# Ethernet.net
KiCad netlist of a schematic drawn in Altium Designer
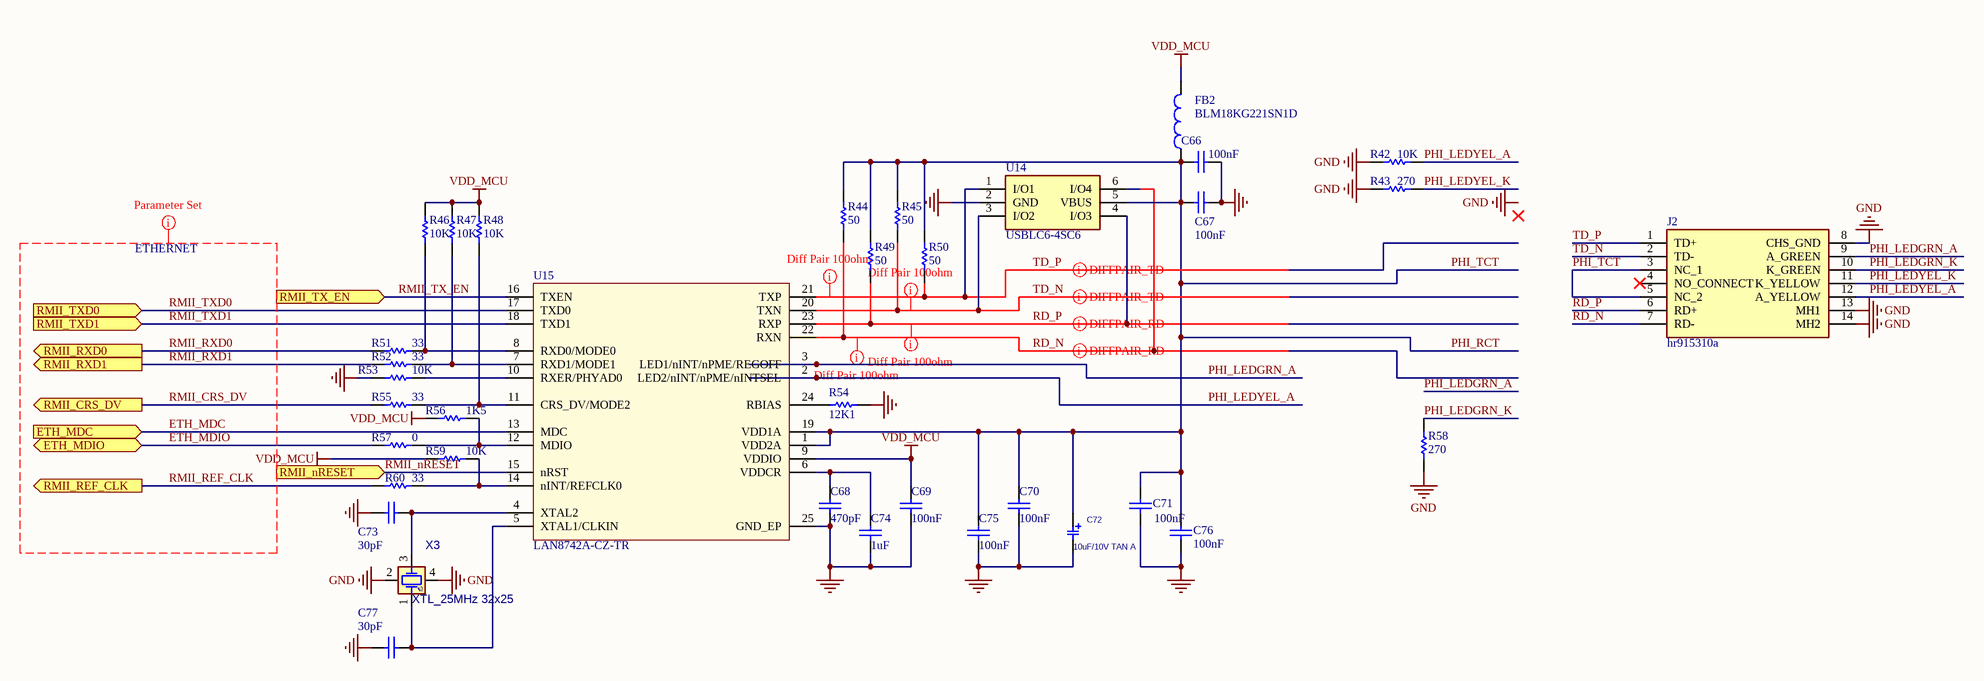
[diagram p0: Ethernet.SchDoc]

(export (version "E")
  (design (tool "Eeschema 10.0.6"))
  (components
    (comp (ref "C66") (value "100nF") (footprint "C0603") (libsource (lib "MCD_TOOLS") (part "Capacitor_ST")))
    (comp (ref "C67") (value "100nF") (footprint "C0603") (libsource (lib "MCD_TOOLS") (part "Capacitor_ST")))
    (comp (ref "C68") (value "470pF") (footprint "C0603") (libsource (lib "MCD_TOOLS") (part "Capacitor_ST")))
    (comp (ref "C69") (value "100nF") (footprint "C0603") (libsource (lib "MCD_TOOLS") (part "Capacitor_ST")))
    (comp (ref "C70") (value "100nF") (footprint "C0603") (libsource (lib "MCD_TOOLS") (part "Capacitor_ST")))
    (comp (ref "C71") (value "100nF") (footprint "C0603") (libsource (lib "MCD_TOOLS") (part "Capacitor_ST")))
    (comp (ref "C72")
      (value "10uF/10V TAN A")
      (footprint "C_TN_3216")
      (description "CAP, SMD, TAN")
      (fields (field (name "MANF") "VISHAY") (field (name "MANF_P#") "T55A106M6R3C0300"))
      (libsource (lib "CapTantal_passive") (part "CAP_SMD_TAN_10uF_6.3V"))
    )
    (comp (ref "C73") (value "30pF") (footprint "C0603") (libsource (lib "MCD_TOOLS") (part "Capacitor_ST")))
    (comp (ref "C74")
      (value "1uF")
      (footprint "C0603")
      (description "0603  X5R 1µF")
      (fields (field (name "TOLERANCE") "10%"))
      (libsource (lib "MB963_1") (part "CAP SMD 0603  X5R 1µF 25V 10%"))
    )
    (comp (ref "C75") (value "100nF") (footprint "C0603") (libsource (lib "MCD_TOOLS") (part "Capacitor_ST")))
    (comp (ref "C76") (value "100nF") (footprint "C0603") (libsource (lib "MCD_TOOLS") (part "Capacitor_ST")))
    (comp (ref "C77") (value "30pF") (footprint "C0603") (libsource (lib "MCD_TOOLS") (part "Capacitor_ST")))
    (comp (ref "FB2")
      (value "BLM18KG221SN1D")
      (footprint "L0603E")
      (description "Ferrite Bead")
      (fields (field (name "PUBLISHER") "Altium Limited"))
      (libsource (lib "Miscellaneous Devices") (part "Inductor"))
    )
    (comp (ref "J2")
      (value "hr915310a")
      (footprint "SamacSys:hr915310a")
      (description "HR915310A")
      (libsource (lib "*") (part "hr915310a"))
    )
    (comp (ref "R42") (value "10K") (footprint "R0603") (libsource (lib "") (part "Res1_1")))
    (comp (ref "R43") (value "270") (footprint "R0603") (libsource (lib "") (part "Res1_1")))
    (comp (ref "R44") (value "50") (footprint "R0603") (libsource (lib "MB1137") (part "Res_50_1%_0603")))
    (comp (ref "R45") (value "50") (footprint "R0603") (libsource (lib "MB1137") (part "Res_50_1%_0603")))
    (comp (ref "R46") (value "10K") (footprint "R0603") (libsource (lib "") (part "Res1_1")))
    (comp (ref "R47") (value "10K") (footprint "R0603") (libsource (lib "") (part "Res1_1")))
    (comp (ref "R48") (value "10K") (footprint "R0603") (libsource (lib "") (part "Res1_1")))
    (comp (ref "R49") (value "50") (footprint "R0603") (libsource (lib "MB1137") (part "Res_50_1%_0603")))
    (comp (ref "R50") (value "50") (footprint "R0603") (libsource (lib "MB1137") (part "Res_50_1%_0603")))
    (comp (ref "R51") (value "33") (footprint "R0603") (libsource (lib "MCD_TOOLS") (part "Res_33_1%_0402")))
    (comp (ref "R52") (value "33") (footprint "R0603") (libsource (lib "MCD_TOOLS") (part "Res_33_1%_0402")))
    (comp (ref "R53") (value "10K") (footprint "R0603") (libsource (lib "") (part "Res1_1")))
    (comp (ref "R54")
      (value "12K1")
      (footprint "R0603")
      (libsource (lib "MCD_TOOLS") (part "Res_12K1_1%_0603"))
    )
    (comp (ref "R55") (value "33") (footprint "R0603") (libsource (lib "MCD_TOOLS") (part "Res_33_1%_0402")))
    (comp (ref "R56")
      (value "1K5")
      (footprint "R0603")
      (libsource (lib "MCD_TOOLS") (part "Res_1K5_1%_0402"))
    )
    (comp (ref "R57")
      (value "0")
      (footprint "R0603")
      (fields (field (name "PUBLISHER") "Altium Limited"))
      (libsource (lib "Miscellaneous Devices") (part "Res1"))
    )
    (comp (ref "R58") (value "270") (footprint "R0603") (libsource (lib "") (part "Res1_1")))
    (comp (ref "R59") (value "10K") (footprint "R0603") (libsource (lib "") (part "Res1_1")))
    (comp (ref "R60") (value "33") (footprint "R0603") (libsource (lib "MCD_TOOLS") (part "Res_33_1%_0402")))
    (comp (ref "U14")
      (value "USBLC6-4SC6")
      (footprint "SamacSys:SOT95P280X145-6N")
      (description "Integrated Circuit")
      (fields (field (name "MOUSER PART NUMBER") "511-USBLC6-4SC6"))
      (libsource (lib "*") (part "USBLC6-4SC6"))
    )
    (comp (ref "U15")
      (value "LAN8742A-CZ-TR")
      (footprint "QFN50P400X400X100-25N-D")
      (libsource (lib "MB1137") (part "LAN8742A-CZ-TR"))
    )
    (comp (ref "X3")
      (value "XTL_25MHz 32x25")
      (footprint "XTL_4_3225")
      (description "CRYSTAL 25.00 MHZ 18pF, 10PPM")
      (fields (field (name "MANF") "EPSON") (field (name "MANF_P#") "TSX-3225 25.0000MF10P-C3"))
      (libsource (lib "crystal_osc") (part "XTL_4_25MHz_3225"))
    )
  )
  (nets
    (net (code "1") (name "/ETH_MDC") (class "Default")
      (node (ref "U15") (pin "13") (pinfunction "MDC_13") (pintype "passive"))
    )
    (net (code "2") (name "/ETH_MDIO") (class "Default")
      (node (ref "R57") (pin "2") (pinfunction "2_2") (pintype "passive"))
    )
    (net (code "3") (name "/PHI_LEDGRN_A") (class "Default")
      (node (ref "J2") (pin "9") (pinfunction "A_GREEN_9") (pintype "passive"))
      (node (ref "U15") (pin "3") (pinfunction "LED1/nINT/nPME/REGOFF_3") (pintype "passive"))
    )
    (net (code "4") (name "/PHI_LEDGRN_K") (class "Default")
      (node (ref "J2") (pin "10") (pinfunction "K_GREEN_10") (pintype "passive"))
      (node (ref "R58") (pin "1") (pinfunction "1_1") (pintype "passive"))
    )
    (net (code "5") (name "/PHI_LEDYEL_A") (class "Default")
      (node (ref "J2") (pin "12") (pinfunction "A_YELLOW_12") (pintype "passive"))
      (node (ref "R42") (pin "2") (pinfunction "2_2") (pintype "passive"))
      (node (ref "U15") (pin "2") (pinfunction "LED2/nINT/nPME/nINTSEL_2") (pintype "passive"))
    )
    (net (code "6") (name "/PHI_LEDYEL_K") (class "Default")
      (node (ref "J2") (pin "11") (pinfunction "K_YELLOW_11") (pintype "passive"))
      (node (ref "R43") (pin "2") (pinfunction "2_2") (pintype "passive"))
    )
    (net (code "7") (name "/PHI_RCT") (class "Default")
      (node (ref "C66") (pin "2") (pinfunction "2_2") (pintype "passive"))
      (node (ref "C67") (pin "2") (pinfunction "2_2") (pintype "passive"))
      (node (ref "C70") (pin "2") (pinfunction "2_2") (pintype "passive"))
      (node (ref "C71") (pin "2") (pinfunction "2_2") (pintype "passive"))
      (node (ref "C72") (pin "1") (pinfunction "1_1") (pintype "passive"))
      (node (ref "C75") (pin "2") (pinfunction "2_2") (pintype "passive"))
      (node (ref "C76") (pin "2") (pinfunction "2_2") (pintype "passive"))
      (node (ref "FB2") (pin "1") (pinfunction "1_1") (pintype "passive"))
      (node (ref "J2") (pin "3") (pinfunction "NC_1_3") (pintype "passive"))
      (node (ref "J2") (pin "5") (pinfunction "NC_2_5") (pintype "passive"))
      (node (ref "R44") (pin "2") (pinfunction "2_2") (pintype "passive"))
      (node (ref "R45") (pin "2") (pinfunction "2_2") (pintype "passive"))
      (node (ref "R49") (pin "2") (pinfunction "2_2") (pintype "passive"))
      (node (ref "R50") (pin "2") (pinfunction "2_2") (pintype "passive"))
      (node (ref "U14") (pin "5") (pinfunction "VBUS_5") (pintype "passive"))
      (node (ref "U15") (pin "1") (pinfunction "VDD2A_1") (pintype "passive"))
      (node (ref "U15") (pin "19") (pinfunction "VDD1A_19") (pintype "passive"))
    )
    (net (code "8") (name "/RD_N") (class "Default")
      (node (ref "J2") (pin "7") (pinfunction "RD-_7") (pintype "passive"))
      (node (ref "R44") (pin "1") (pinfunction "1_1") (pintype "passive"))
      (node (ref "U14") (pin "6") (pinfunction "I/O4_6") (pintype "passive"))
      (node (ref "U15") (pin "22") (pinfunction "RXN_22") (pintype "passive"))
    )
    (net (code "9") (name "/RD_P") (class "Default")
      (node (ref "J2") (pin "6") (pinfunction "RD+_6") (pintype "passive"))
      (node (ref "R49") (pin "1") (pinfunction "1_1") (pintype "passive"))
      (node (ref "U14") (pin "4") (pinfunction "I/O3_4") (pintype "passive"))
      (node (ref "U15") (pin "23") (pinfunction "RXP_23") (pintype "passive"))
    )
    (net (code "10") (name "/RMII_CRS_DV") (class "Default")
      (node (ref "R55") (pin "2") (pinfunction "2_2") (pintype "passive"))
    )
    (net (code "11") (name "/RMII_REF_CLK") (class "Default")
      (node (ref "R60") (pin "2") (pinfunction "2_2") (pintype "passive"))
    )
    (net (code "12") (name "/RMII_RXD0") (class "Default")
      (node (ref "R51") (pin "2") (pinfunction "2_2") (pintype "passive"))
    )
    (net (code "13") (name "/RMII_RXD1") (class "Default")
      (node (ref "R52") (pin "2") (pinfunction "2_2") (pintype "passive"))
    )
    (net (code "14") (name "/RMII_TXD0") (class "Default")
      (node (ref "U15") (pin "17") (pinfunction "TXD0_17") (pintype "passive"))
    )
    (net (code "15") (name "/RMII_TXD1") (class "Default")
      (node (ref "U15") (pin "18") (pinfunction "TXD1_18") (pintype "passive"))
    )
    (net (code "16") (name "/RMII_TX_EN") (class "Default")
      (node (ref "U15") (pin "16") (pinfunction "TXEN_16") (pintype "passive"))
    )
    (net (code "17") (name "/RMII_nRESET") (class "Default")
      (node (ref "U15") (pin "15") (pinfunction "nRST_15") (pintype "passive"))
    )
    (net (code "18") (name "/TD_N") (class "Default")
      (node (ref "J2") (pin "2") (pinfunction "TD-_2") (pintype "passive"))
      (node (ref "R45") (pin "1") (pinfunction "1_1") (pintype "passive"))
      (node (ref "U14") (pin "3") (pinfunction "I/O2_3") (pintype "passive"))
      (node (ref "U15") (pin "20") (pinfunction "TXN_20") (pintype "passive"))
    )
    (net (code "19") (name "/TD_P") (class "Default")
      (node (ref "J2") (pin "1") (pinfunction "TD+_1") (pintype "passive"))
      (node (ref "R50") (pin "1") (pinfunction "1_1") (pintype "passive"))
      (node (ref "U14") (pin "1") (pinfunction "I/O1_1") (pintype "passive"))
      (node (ref "U15") (pin "21") (pinfunction "TXP_21") (pintype "passive"))
    )
    (net (code "20") (name "GND") (class "Default")
      (node (ref "C66") (pin "1") (pinfunction "1_1") (pintype "passive"))
      (node (ref "C67") (pin "1") (pinfunction "1_1") (pintype "passive"))
      (node (ref "C68") (pin "1") (pinfunction "1_1") (pintype "passive"))
      (node (ref "C69") (pin "1") (pinfunction "1_1") (pintype "passive"))
      (node (ref "C70") (pin "1") (pinfunction "1_1") (pintype "passive"))
      (node (ref "C71") (pin "1") (pinfunction "1_1") (pintype "passive"))
      (node (ref "C72") (pin "2") (pinfunction "2_2") (pintype "passive"))
      (node (ref "C73") (pin "2") (pinfunction "2_2") (pintype "passive"))
      (node (ref "C74") (pin "2") (pinfunction "2_2") (pintype "passive"))
      (node (ref "C75") (pin "1") (pinfunction "1_1") (pintype "passive"))
      (node (ref "C76") (pin "1") (pinfunction "1_1") (pintype "passive"))
      (node (ref "C77") (pin "2") (pinfunction "2_2") (pintype "passive"))
      (node (ref "J2") (pin "13") (pinfunction "MH1_13") (pintype "passive"))
      (node (ref "J2") (pin "14") (pinfunction "MH2_14") (pintype "passive"))
      (node (ref "J2") (pin "8") (pinfunction "CHS_GND_8") (pintype "passive"))
      (node (ref "R42") (pin "1") (pinfunction "1_1") (pintype "passive"))
      (node (ref "R43") (pin "1") (pinfunction "1_1") (pintype "passive"))
      (node (ref "R53") (pin "2") (pinfunction "2_2") (pintype "passive"))
      (node (ref "R54") (pin "2") (pinfunction "2_2") (pintype "passive"))
      (node (ref "R58") (pin "2") (pinfunction "2_2") (pintype "passive"))
      (node (ref "U14") (pin "2") (pinfunction "GND_2") (pintype "passive"))
      (node (ref "U15") (pin "25") (pinfunction "GND_EP_25") (pintype "passive"))
      (node (ref "X3") (pin "2") (pinfunction "GND1_2") (pintype "passive"))
      (node (ref "X3") (pin "4") (pinfunction "GND2_4") (pintype "passive"))
    )
    (net (code "21") (name "Net-(U15-CRS_DV{slash}MODE2)") (class "Default")
      (node (ref "R48") (pin "2") (pinfunction "2_2") (pintype "passive"))
      (node (ref "R55") (pin "1") (pinfunction "1_1") (pintype "passive"))
      (node (ref "U15") (pin "11") (pinfunction "CRS_DV/MODE2_11") (pintype "passive"))
    )
    (net (code "22") (name "Net-(U15-MDIO)") (class "Default")
      (node (ref "R56") (pin "1") (pinfunction "1_1") (pintype "passive"))
      (node (ref "R57") (pin "1") (pinfunction "1_1") (pintype "passive"))
      (node (ref "U15") (pin "12") (pinfunction "MDIO_12") (pintype "passive"))
    )
    (net (code "23") (name "Net-(U15-RBIAS)") (class "Default")
      (node (ref "R54") (pin "1") (pinfunction "1_1") (pintype "passive"))
      (node (ref "U15") (pin "24") (pinfunction "RBIAS_24") (pintype "passive"))
    )
    (net (code "24") (name "Net-(U15-RXD0{slash}MODE0)") (class "Default")
      (node (ref "R46") (pin "2") (pinfunction "2_2") (pintype "passive"))
      (node (ref "R51") (pin "1") (pinfunction "1_1") (pintype "passive"))
      (node (ref "U15") (pin "8") (pinfunction "RXD0/MODE0_8") (pintype "passive"))
    )
    (net (code "25") (name "Net-(U15-RXD1{slash}MODE1)") (class "Default")
      (node (ref "R47") (pin "2") (pinfunction "2_2") (pintype "passive"))
      (node (ref "R52") (pin "1") (pinfunction "1_1") (pintype "passive"))
      (node (ref "U15") (pin "7") (pinfunction "RXD1/MODE1_7") (pintype "passive"))
    )
    (net (code "26") (name "Net-(U15-RXER{slash}PHYAD0)") (class "Default")
      (node (ref "R53") (pin "1") (pinfunction "1_1") (pintype "passive"))
      (node (ref "U15") (pin "10") (pinfunction "RXER/PHYAD0_10") (pintype "passive"))
    )
    (net (code "27") (name "Net-(U15-VDDCR)") (class "Default")
      (node (ref "C68") (pin "2") (pinfunction "2_2") (pintype "passive"))
      (node (ref "C74") (pin "1") (pinfunction "1_1") (pintype "passive"))
      (node (ref "U15") (pin "6") (pinfunction "VDDCR_6") (pintype "passive"))
    )
    (net (code "28") (name "Net-(U15-XTAL1{slash}CLKIN)") (class "Default")
      (node (ref "C77") (pin "1") (pinfunction "1_1") (pintype "passive"))
      (node (ref "U15") (pin "5") (pinfunction "XTAL1/CLKIN_5") (pintype "passive"))
      (node (ref "X3") (pin "1") (pinfunction "XA_1") (pintype "passive"))
    )
    (net (code "29") (name "Net-(U15-XTAL2)") (class "Default")
      (node (ref "C73") (pin "1") (pinfunction "1_1") (pintype "passive"))
      (node (ref "U15") (pin "4") (pinfunction "XTAL2_4") (pintype "passive"))
      (node (ref "X3") (pin "3") (pinfunction "XB_3") (pintype "passive"))
    )
    (net (code "30") (name "Net-(U15-nINT{slash}REFCLK0)") (class "Default")
      (node (ref "R59") (pin "2") (pinfunction "2_2") (pintype "passive"))
      (node (ref "R60") (pin "1") (pinfunction "1_1") (pintype "passive"))
      (node (ref "U15") (pin "14") (pinfunction "nINT/REFCLK0_14") (pintype "passive"))
    )
    (net (code "31") (name "VDD_MCU") (class "Default")
      (node (ref "C69") (pin "2") (pinfunction "2_2") (pintype "passive"))
      (node (ref "FB2") (pin "2") (pinfunction "2_2") (pintype "passive"))
      (node (ref "R46") (pin "1") (pinfunction "1_1") (pintype "passive"))
      (node (ref "R47") (pin "1") (pinfunction "1_1") (pintype "passive"))
      (node (ref "R48") (pin "1") (pinfunction "1_1") (pintype "passive"))
      (node (ref "R56") (pin "2") (pinfunction "2_2") (pintype "passive"))
      (node (ref "R59") (pin "1") (pinfunction "1_1") (pintype "passive"))
      (node (ref "U15") (pin "9") (pinfunction "VDDIO_9") (pintype "passive"))
    )
    (net (code "32") (name "unconnected-(J2-NO_CONNECT-Pad4)") (class "Default")
      (node (ref "J2") (pin "4") (pinfunction "NO_CONNECT_4") (pintype "passive+no_connect"))
    )
  )
)
